# linkit-v4.net
KiCad netlist of a schematic drawn in Altium Designer
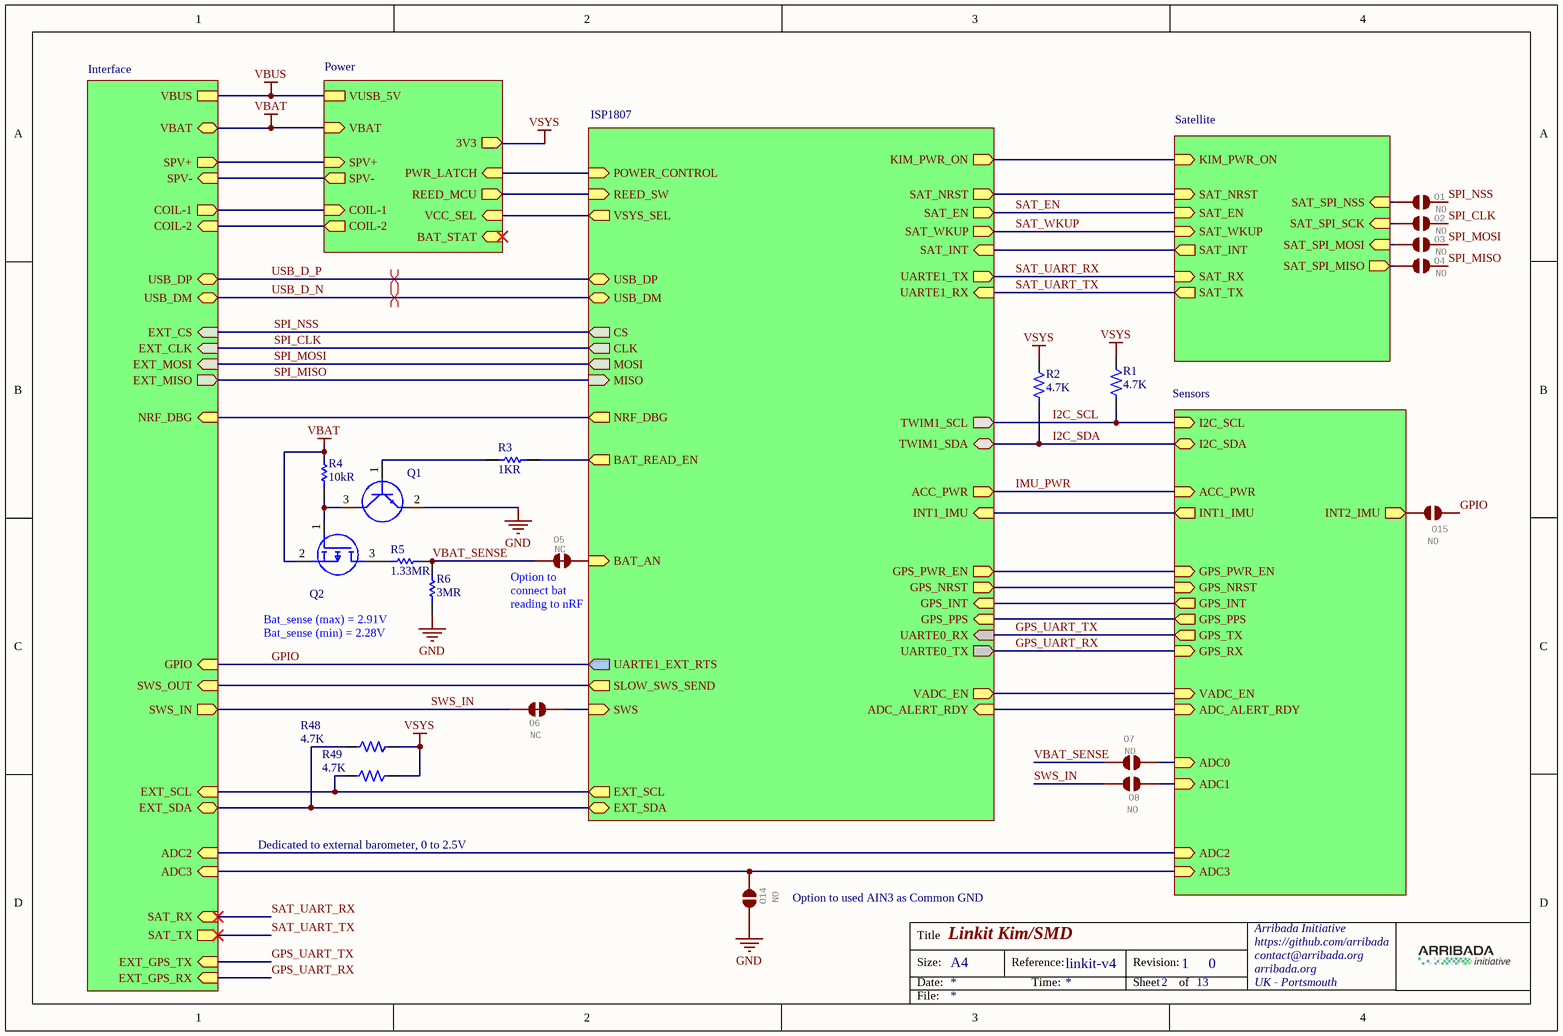
[diagram p0: linkit-v4.SchDoc]

(export (version "E")
  (design (tool "Eeschema 10.0.6"))
  (components
    (comp (ref "O1")
      (value "NO")
      (footprint "SMT-JUMPER_2_NO_TRACE_SILK")
      (libsource (lib "stm32wl-dev") (part "JUMPER-SMT_2_NO_TRACE_SILK_1"))
    )
    (comp (ref "O2")
      (value "NO")
      (footprint "SMT-JUMPER_2_NO_TRACE_SILK")
      (libsource (lib "stm32wl-dev") (part "JUMPER-SMT_2_NO_TRACE_SILK_1"))
    )
    (comp (ref "O3")
      (value "NO")
      (footprint "SMT-JUMPER_2_NO_TRACE_SILK")
      (libsource (lib "stm32wl-dev") (part "JUMPER-SMT_2_NO_TRACE_SILK_1"))
    )
    (comp (ref "O4")
      (value "NO")
      (footprint "SMT-JUMPER_2_NO_TRACE_SILK")
      (libsource (lib "stm32wl-dev") (part "JUMPER-SMT_2_NO_TRACE_SILK_1"))
    )
    (comp (ref "O5")
      (value "NC")
      (footprint "SMT-JUMPER_2_NC_TRACE_SILK")
      (libsource (lib "stm32wl-dev") (part "JUMPER-SMT_2_NC_TRACE_SILK"))
    )
    (comp (ref "O6")
      (value "NC")
      (footprint "SMT-JUMPER_2_NC_TRACE_SILK")
      (libsource (lib "stm32wl-dev") (part "JUMPER-SMT_2_NC_TRACE_SILK"))
    )
    (comp (ref "O7")
      (value "NO")
      (footprint "SMT-JUMPER_2_NO_TRACE_SILK")
      (libsource (lib "stm32wl-dev") (part "JUMPER-SMT_2_NO_TRACE_SILK_1"))
    )
    (comp (ref "O8")
      (value "NO")
      (footprint "SMT-JUMPER_2_NO_TRACE_SILK")
      (libsource (lib "stm32wl-dev") (part "JUMPER-SMT_2_NO_TRACE_SILK_1"))
    )
    (comp (ref "O14")
      (value "NO")
      (footprint "SMT-JUMPER_2_NO_TRACE_SILK")
      (libsource (lib "stm32wl-dev") (part "JUMPER-SMT_2_NO_TRACE_SILK_1"))
    )
    (comp (ref "O15")
      (value "NO")
      (footprint "SMT-JUMPER_2_NO_TRACE_SILK")
      (libsource (lib "stm32wl-dev") (part "JUMPER-SMT_2_NO_TRACE_SILK_1"))
    )
    (comp (ref "Q1")
      (value "MMBT3904LT1G")
      (footprint "stm32wl-dev:SOT96P237X111-3N")
      (description "Bipolar Transistors - BJT NPN GENERAL PURPOSE")
      (fields (field (name "MOUSER PART NUMBER") "863-MMBT3904LT1G"))
      (libsource (lib "stm32wl-dev") (part "MMBT3904LT1G"))
    )
    (comp (ref "Q2")
      (value "DMP2305U-7")
      (footprint "stm32wl-dev:SOT96P240X115-3N")
      (description "MOSFET P-CHANNEL ENHANCEMENT MODE")
      (fields (field (name "MOUSER PART NUMBER") "621-DMP2305U-7"))
      (libsource (lib "stm32wl-dev") (part "DMP2305U-7"))
    )
    (comp (ref "R1")
      (value "4.7K")
      (footprint "RES0201L")
      (description "RES 4.7K 0201 1% 100PPM")
      (fields (field (name "TOLERANCE") "1%") (field (name "Comment") "4.7K 0201 1% 100PPM"))
      (libsource (lib "Resistors") (part "RES 4.7K 0201 1% 100PPM"))
    )
    (comp (ref "R2")
      (value "4.7K")
      (footprint "RES0201L")
      (description "RES 4.7K 0201 1% 100PPM")
      (fields (field (name "TOLERANCE") "1%") (field (name "Comment") "4.7K 0201 1% 100PPM"))
      (libsource (lib "Resistors") (part "RES 4.7K 0201 1% 100PPM"))
    )
    (comp (ref "R3")
      (value "1KR")
      (footprint "RESC0603X28N")
      (description "Thick Film Resistors - SMD 1/20watt 1Kohms 1% 200ppm")
      (fields
        (field (name "MANUFACTURER_PART_NUMBER") "CRCW02011K00FNED")
        (field (name "MOUSER PART NUMBER") "71-CRCW02011K00FNED")
      )
      (libsource (lib "stm32wl-dev") (part "CRCW02011K00FNED"))
    )
    (comp (ref "R4")
      (value "10kR")
      (footprint "RESC1005X40N")
      (description "Thick Film Resistors - SMD 1/16watt 10Kohms 5% Commercial Use")
      (fields
        (field (name "MANUFACTURER") "Vishay Semiconductors")
        (field (name "MANUFACTURER PART NUMBER") "CRCW040210K0JNEDC")
      )
      (libsource (lib "stm32wl-dev") (part "CRCW040210K0JNEDC"))
    )
    (comp (ref "R5")
      (value "1.33MR")
      (footprint "RESC2012X60N")
      (description "Thin Film Resistors - SMD 1/8W 1.33M Ohms 0.1%")
      (fields
        (field (name "MANUFACTURER") "Yageo")
        (field (name "MANUFACTURER PART NUMBER") "RT0805BRD071M33L")
      )
      (libsource (lib "stm32wl-dev") (part "RT0805BRD071M33L"))
    )
    (comp (ref "R6")
      (value "3MR")
      (footprint "stm32wl-dev:RESC3216X55N")
      (fields (field (name "MANUFACTURER_PART_NUMBER") "RGV3216P-3004-B-T1"))
      (libsource (lib "stm32wl-dev") (part "RGV3216P-3004-B-T1"))
    )
    (comp (ref "R48")
      (value "4.7K")
      (footprint "RES0201L")
      (description "RES 4.7K 0201 1% 100PPM")
      (fields (field (name "TOLERANCE") "1%") (field (name "Comment") "4.7K 0201 1% 100PPM"))
      (libsource (lib "Resistors") (part "RES 4.7K 0201 1% 100PPM"))
    )
    (comp (ref "R49")
      (value "4.7K")
      (footprint "RES0201L")
      (description "RES 4.7K 0201 1% 100PPM")
      (fields (field (name "TOLERANCE") "1%") (field (name "Comment") "4.7K 0201 1% 100PPM"))
      (libsource (lib "Resistors") (part "RES 4.7K 0201 1% 100PPM"))
    )
  )
  (nets
    (net (code "1") (name "/ADC0") (class "Default")
      (node (ref "O7") (pin "2") (pinfunction "2_2") (pintype "passive"))
    )
    (net (code "2") (name "/ADC1") (class "Default")
      (node (ref "O8") (pin "2") (pinfunction "2_2") (pintype "passive"))
    )
    (net (code "4") (name "/ADC3") (class "Default")
      (node (ref "O14") (pin "2") (pinfunction "2_2") (pintype "passive"))
    )
    (net (code "6") (name "/BAT_AN") (class "Default")
      (node (ref "O5") (pin "2") (pinfunction "2_2") (pintype "passive"))
    )
    (net (code "7") (name "/BAT_READ_EN") (class "Default")
      (node (ref "R3") (pin "2") (pinfunction "2_2") (pintype "passive"))
    )
    (net (code "11") (name "/EXT_SCL") (class "Default")
      (node (ref "R49") (pin "2") (pinfunction "2_2") (pintype "passive"))
    )
    (net (code "12") (name "/EXT_SDA") (class "Default")
      (node (ref "R48") (pin "1") (pinfunction "1_1") (pintype "passive"))
    )
    (net (code "13") (name "/GPIO") (class "Default")
      (node (ref "O15") (pin "1") (pinfunction "1_1") (pintype "passive"))
    )
    (net (code "20") (name "/I2C_SCL") (class "Default")
      (node (ref "R1") (pin "1") (pinfunction "1_1") (pintype "passive"))
    )
    (net (code "21") (name "/I2C_SDA") (class "Default")
      (node (ref "R2") (pin "1") (pinfunction "1_1") (pintype "passive"))
    )
    (net (code "32") (name "/SAT_SPI_MISO") (class "Default")
      (node (ref "O4") (pin "1") (pinfunction "1_1") (pintype "passive"))
    )
    (net (code "33") (name "/SAT_SPI_MOSI") (class "Default")
      (node (ref "O3") (pin "1") (pinfunction "1_1") (pintype "passive"))
    )
    (net (code "34") (name "/SAT_SPI_NSS") (class "Default")
      (node (ref "O1") (pin "1") (pinfunction "1_1") (pintype "passive"))
    )
    (net (code "35") (name "/SAT_SPI_SCK") (class "Default")
      (node (ref "O2") (pin "1") (pinfunction "1_1") (pintype "passive"))
    )
    (net (code "40") (name "/SPI_CLK") (class "Default")
      (node (ref "O2") (pin "2") (pinfunction "2_2") (pintype "passive"))
    )
    (net (code "41") (name "/SPI_MISO") (class "Default")
      (node (ref "O4") (pin "2") (pinfunction "2_2") (pintype "passive"))
    )
    (net (code "42") (name "/SPI_MOSI") (class "Default")
      (node (ref "O3") (pin "2") (pinfunction "2_2") (pintype "passive"))
    )
    (net (code "43") (name "/SPI_NSS") (class "Default")
      (node (ref "O1") (pin "2") (pinfunction "2_2") (pintype "passive"))
    )
    (net (code "46") (name "/SWS") (class "Default")
      (node (ref "O6") (pin "2") (pinfunction "2_2") (pintype "passive"))
    )
    (net (code "47") (name "/SWS_IN") (class "Default")
      (node (ref "O6") (pin "1") (pinfunction "1_1") (pintype "passive"))
      (node (ref "O8") (pin "1") (pinfunction "1_1") (pintype "passive"))
    )
    (net (code "51") (name "/VBAT_SENSE") (class "Default")
      (node (ref "O5") (pin "1") (pinfunction "1_1") (pintype "passive"))
      (node (ref "O7") (pin "1") (pinfunction "1_1") (pintype "passive"))
      (node (ref "R5") (pin "2") (pinfunction "2_2") (pintype "passive"))
      (node (ref "R6") (pin "1") (pinfunction "1_1") (pintype "passive"))
    )
    (net (code "53") (name "GND") (class "Default")
      (node (ref "O14") (pin "1") (pinfunction "1_1") (pintype "passive"))
      (node (ref "Q1") (pin "2") (pinfunction "E_2") (pintype "passive"))
      (node (ref "R6") (pin "2") (pinfunction "2_2") (pintype "passive"))
    )
    (net (code "54") (name "Net-(Q1-B)") (class "Default")
      (node (ref "Q1") (pin "1") (pinfunction "B_1") (pintype "passive"))
      (node (ref "R3") (pin "1") (pinfunction "1_1") (pintype "passive"))
    )
    (net (code "55") (name "Net-(Q1-C)") (class "Default")
      (node (ref "Q1") (pin "3") (pinfunction "C_3") (pintype "passive"))
      (node (ref "Q2") (pin "1") (pinfunction "G_1") (pintype "passive"))
      (node (ref "R4") (pin "2") (pinfunction "2_2") (pintype "passive"))
    )
    (net (code "56") (name "Net-(Q2-D)") (class "Default")
      (node (ref "Q2") (pin "3") (pinfunction "D_3") (pintype "passive"))
      (node (ref "R5") (pin "1") (pinfunction "1_1") (pintype "passive"))
    )
    (net (code "57") (name "VBAT") (class "Default")
      (node (ref "Q2") (pin "2") (pinfunction "S_2") (pintype "passive"))
      (node (ref "R4") (pin "1") (pinfunction "1_1") (pintype "passive"))
    )
    (net (code "59") (name "VSYS") (class "Default")
      (node (ref "R1") (pin "2") (pinfunction "2_2") (pintype "passive"))
      (node (ref "R2") (pin "2") (pinfunction "2_2") (pintype "passive"))
      (node (ref "R48") (pin "2") (pinfunction "2_2") (pintype "passive"))
      (node (ref "R49") (pin "1") (pinfunction "1_1") (pintype "passive"))
    )
    (net (code "60") (name "unconnected-(O15-Pad2)") (class "Default")
      (node (ref "O15") (pin "2") (pinfunction "2_2") (pintype "passive"))
    )
  )
)
